# IR_remote_2_1.net
KiCad netlist of a schematic drawn in EAGLE
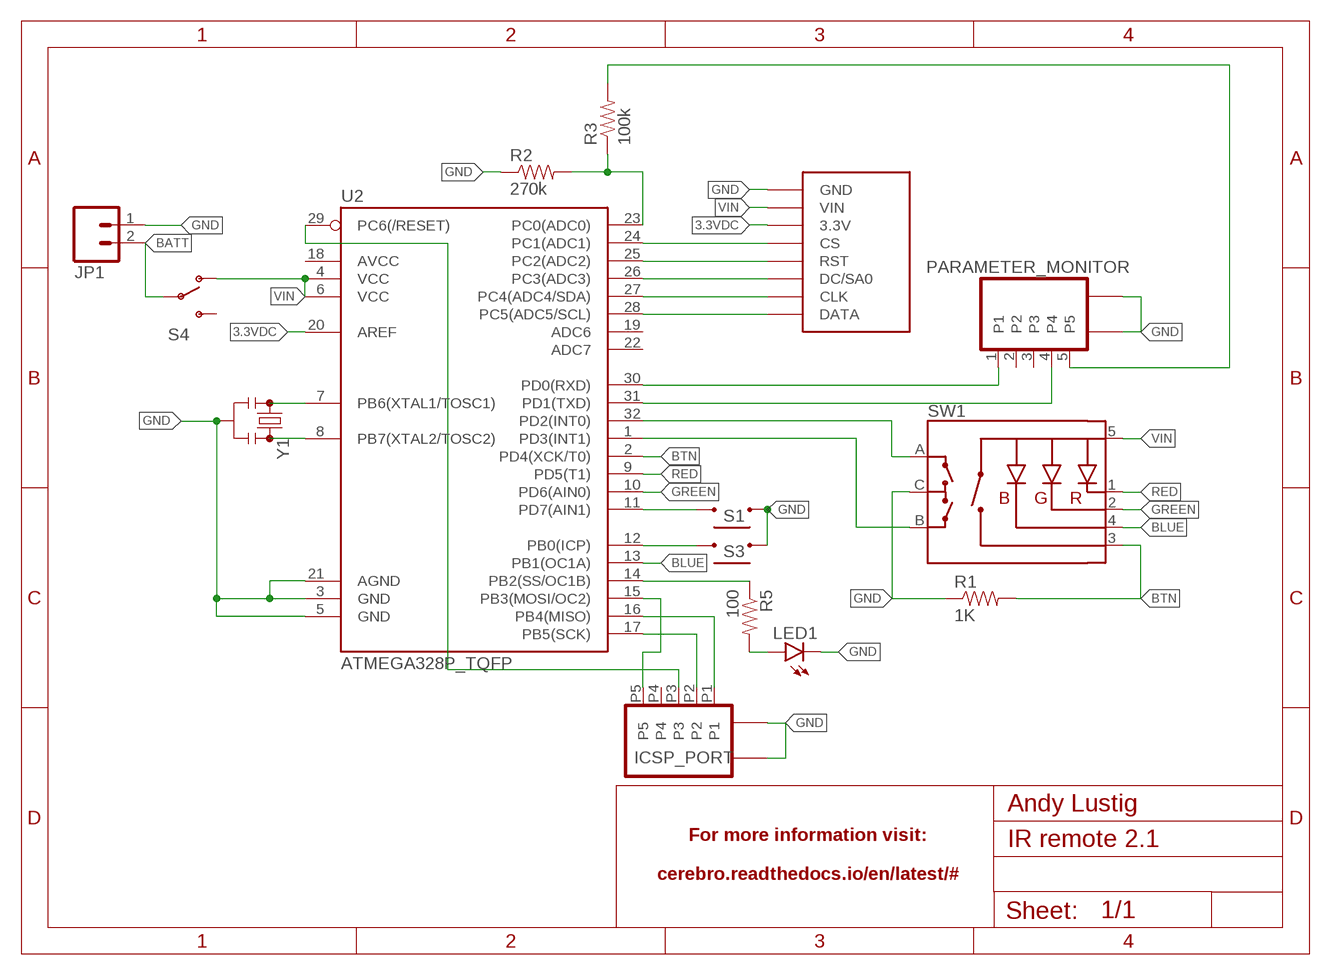
[diagram p0: schematic, sheet 1]

(export (version "E")
  (design (tool "Eeschema 10.0.6"))
  (components
    (comp (ref "ICSP_PORT")
      (value "USB_SOCKET_MICRO_VERTREINFORCED")
      (footprint "eagle-import:USB_HORZ_REINFORCED_MICRO")
      (libsource (lib "eagle-import") (part "USB_SOCKET_MICRO_VERTREINFORCED"))
    )
    (comp (ref "JP1")
      (value "M02JST-PTH-2")
      (footprint "eagle-import:JST-2-PTH")
      (libsource (lib "eagle-import") (part "M02JST-PTH-2"))
    )
    (comp (ref "LED1")
      (value "LED5MM-KIT")
      (footprint "eagle-import:LED5MM-KIT")
      (libsource (lib "eagle-import") (part "LED5MM-KIT"))
    )
    (comp (ref "PARAMETER_MONITOR")
      (value "USB_MICROB_PLUG-PTH2")
      (footprint "eagle-import:MICRO-B-TH")
      (libsource (lib "eagle-import") (part "USB_MICROB_PLUG-PTH2"))
    )
    (comp (ref "R1")
      (value "1K")
      (footprint "eagle-import:AXIAL-0.1")
      (libsource (lib "eagle-import") (part "RESISTORPTH-1/4W-VERT"))
    )
    (comp (ref "R2")
      (value "270k")
      (footprint "eagle-import:AXIAL-0.1")
      (libsource (lib "eagle-import") (part "RESISTORPTH-1/4W-VERT"))
    )
    (comp (ref "R3")
      (value "100k")
      (footprint "eagle-import:AXIAL-0.1")
      (libsource (lib "eagle-import") (part "RESISTORPTH-1/4W-VERT"))
    )
    (comp (ref "R5")
      (value "100")
      (footprint "eagle-import:AXIAL-0.1")
      (libsource (lib "eagle-import") (part "RESISTORPTH-1/4W-VERT"))
    )
    (comp (ref "S1")
      (value "SWITCH-MOMENTARY-2-CLOSED")
      (footprint "eagle-import:TACTILE-PTH-12MM")
      (libsource (lib "eagle-import") (part "SWITCH-MOMENTARY-2-CLOSED"))
    )
    (comp (ref "S3")
      (value "SWITCH-MOMENTARY-2-CLOSED")
      (footprint "eagle-import:TACTILE-PTH-12MM")
      (libsource (lib "eagle-import") (part "SWITCH-MOMENTARY-2-CLOSED"))
    )
    (comp (ref "S4")
      (value "SWITCH-SPDT")
      (footprint "eagle-import:TOGGLE")
      (libsource (lib "eagle-import") (part "SWITCH-SPDT"))
    )
    (comp (ref "SW1")
      (value "ENCODER_RGB_CAKIT")
      (footprint "eagle-import:ENCODER_LED_3_KIT")
      (libsource (lib "eagle-import") (part "ENCODER_RGB_CAKIT"))
    )
    (comp (ref "U$1")
      (value "OLED_DISPLAY")
      (footprint "eagle-import:OLED_DISPLAY")
      (libsource (lib "eagle-import") (part "OLED_DISPLAY"))
    )
    (comp (ref "U2")
      (value "ATMEGA328P_TQFP")
      (footprint "eagle-import:TQFP32-08")
      (libsource (lib "eagle-import") (part "ATMEGA328P_TQFP"))
    )
    (comp (ref "Y1")
      (value "RESONATORPTH")
      (footprint "eagle-import:RESONATOR-PTH")
      (libsource (lib "eagle-import") (part "RESONATORPTH"))
    )
  )
  (nets
    (net (code "1") (name "3.3VDC") (class "Default")
      (node (ref "U$1") (pin "3V3") (pinfunction "3.3V_3V3") (pintype "power_in"))
      (node (ref "U2") (pin "20") (pinfunction "AREF_20") (pintype "bidirectional"))
    )
    (net (code "2") (name "BATT") (class "Default")
      (node (ref "JP1") (pin "2") (pinfunction "2_2") (pintype "passive"))
      (node (ref "S4") (pin "P$2") (pinfunction "P_P$2") (pintype "passive"))
    )
    (net (code "3") (name "BLUE") (class "Default")
      (node (ref "SW1") (pin "4") (pinfunction "-B_4") (pintype "passive"))
      (node (ref "U2") (pin "13") (pinfunction "PB1(OC1A)_13") (pintype "bidirectional"))
    )
    (net (code "4") (name "BTN") (class "Default")
      (node (ref "R1") (pin "P$2") (pinfunction "2_P$2") (pintype "passive"))
      (node (ref "SW1") (pin "3") (pinfunction "SW_3") (pintype "passive"))
      (node (ref "U2") (pin "2") (pinfunction "PD4(XCK/T0)_2") (pintype "bidirectional"))
    )
    (net (code "5") (name "GND") (class "Default")
      (node (ref "ICSP_PORT") (pin "G1") (pinfunction "P$1_G1") (pintype "bidirectional"))
      (node (ref "ICSP_PORT") (pin "G2") (pinfunction "P$1_G2") (pintype "bidirectional"))
      (node (ref "ICSP_PORT") (pin "P$1") (pinfunction "P$2_P$1") (pintype "bidirectional"))
      (node (ref "ICSP_PORT") (pin "P$2") (pinfunction "P$2_P$2") (pintype "bidirectional"))
      (node (ref "JP1") (pin "1") (pinfunction "1_1") (pintype "passive"))
      (node (ref "LED1") (pin "K") (pinfunction "C_K") (pintype "passive"))
      (node (ref "PARAMETER_MONITOR") (pin "P$1") (pinfunction "P$1_P$1") (pintype "bidirectional"))
      (node (ref "PARAMETER_MONITOR") (pin "P$2") (pinfunction "P$2_P$2") (pintype "bidirectional"))
      (node (ref "R1") (pin "P$1") (pinfunction "1_P$1") (pintype "passive"))
      (node (ref "R2") (pin "P$1") (pinfunction "1_P$1") (pintype "passive"))
      (node (ref "S1") (pin "3") (pinfunction "2_3") (pintype "passive"))
      (node (ref "S3") (pin "3") (pinfunction "2_3") (pintype "passive"))
      (node (ref "SW1") (pin "C") (pinfunction "C_C") (pintype "bidirectional"))
      (node (ref "U$1") (pin "GND") (pinfunction "GND_GND") (pintype "bidirectional"))
      (node (ref "U2") (pin "21") (pinfunction "AGND_21") (pintype "bidirectional"))
      (node (ref "U2") (pin "3") (pinfunction "GND_3") (pintype "bidirectional"))
      (node (ref "U2") (pin "5") (pinfunction "GND_5") (pintype "bidirectional"))
      (node (ref "Y1") (pin "2") (pinfunction "2_2") (pintype "passive"))
    )
    (net (code "6") (name "GREEN") (class "Default")
      (node (ref "SW1") (pin "2") (pinfunction "-G_2") (pintype "passive"))
      (node (ref "U2") (pin "10") (pinfunction "PD6(AIN0)_10") (pintype "bidirectional"))
    )
    (net (code "7") (name "Net-(PARAMETER_MONITOR-P1)") (class "Default")
      (node (ref "PARAMETER_MONITOR") (pin "1") (pinfunction "P1_1") (pintype "bidirectional"))
      (node (ref "U2") (pin "30") (pinfunction "PD0(RXD)_30") (pintype "bidirectional"))
    )
    (net (code "8") (name "Net-(PARAMETER_MONITOR-P4)") (class "Default")
      (node (ref "PARAMETER_MONITOR") (pin "4") (pinfunction "P4_4") (pintype "bidirectional"))
      (node (ref "U2") (pin "31") (pinfunction "PD1(TXD)_31") (pintype "bidirectional"))
    )
    (net (code "9") (name "Net-(PARAMETER_MONITOR-P5)") (class "Default")
      (node (ref "PARAMETER_MONITOR") (pin "5") (pinfunction "P5_5") (pintype "bidirectional"))
      (node (ref "R3") (pin "P$2") (pinfunction "2_P$2") (pintype "passive"))
    )
    (net (code "10") (name "Net-(R2-2)") (class "Default")
      (node (ref "R2") (pin "P$2") (pinfunction "2_P$2") (pintype "passive"))
      (node (ref "R3") (pin "P$1") (pinfunction "1_P$1") (pintype "passive"))
      (node (ref "U2") (pin "23") (pinfunction "PC0(ADC0)_23") (pintype "bidirectional"))
    )
    (net (code "11") (name "Net-(R5-1)") (class "Default")
      (node (ref "R5") (pin "P$1") (pinfunction "1_P$1") (pintype "passive"))
      (node (ref "U2") (pin "14") (pinfunction "PB2(SS/OC1B)_14") (pintype "bidirectional"))
    )
    (net (code "12") (name "Net-(R5-2)") (class "Default")
      (node (ref "LED1") (pin "A") (pinfunction "A_A") (pintype "passive"))
      (node (ref "R5") (pin "P$2") (pinfunction "2_P$2") (pintype "passive"))
    )
    (net (code "13") (name "Net-(U$1-DC{slash}SA0)") (class "Default")
      (node (ref "U$1") (pin "DC") (pinfunction "DC/SA0_DC") (pintype "bidirectional"))
      (node (ref "U2") (pin "26") (pinfunction "PC3(ADC3)_26") (pintype "bidirectional"))
    )
    (net (code "14") (name "Net-(U2-PB0(ICP))") (class "Default")
      (node (ref "S3") (pin "1") (pinfunction "1_1") (pintype "passive"))
      (node (ref "U2") (pin "12") (pinfunction "PB0(ICP)_12") (pintype "bidirectional"))
    )
    (net (code "15") (name "Net-(U2-PB3(MOSI{slash}OC2))") (class "Default")
      (node (ref "ICSP_PORT") (pin "P5") (pinfunction "P5_P5") (pintype "bidirectional"))
      (node (ref "U2") (pin "15") (pinfunction "PB3(MOSI/OC2)_15") (pintype "bidirectional"))
    )
    (net (code "16") (name "Net-(U2-PB4(MISO))") (class "Default")
      (node (ref "ICSP_PORT") (pin "P1") (pinfunction "P1_P1") (pintype "bidirectional"))
      (node (ref "U2") (pin "16") (pinfunction "PB4(MISO)_16") (pintype "bidirectional"))
    )
    (net (code "17") (name "Net-(U2-PB5(SCK))") (class "Default")
      (node (ref "ICSP_PORT") (pin "P2") (pinfunction "P2_P2") (pintype "bidirectional"))
      (node (ref "U2") (pin "17") (pinfunction "PB5(SCK)_17") (pintype "bidirectional"))
    )
    (net (code "18") (name "Net-(U2-PB6(XTAL1{slash}TOSC1))") (class "Default")
      (node (ref "U2") (pin "7") (pinfunction "PB6(XTAL1/TOSC1)_7") (pintype "bidirectional"))
      (node (ref "Y1") (pin "1") (pinfunction "1_1") (pintype "passive"))
    )
    (net (code "19") (name "Net-(U2-PB7(XTAL2{slash}TOSC2))") (class "Default")
      (node (ref "U2") (pin "8") (pinfunction "PB7(XTAL2/TOSC2)_8") (pintype "bidirectional"))
      (node (ref "Y1") (pin "3") (pinfunction "3_3") (pintype "passive"))
    )
    (net (code "20") (name "Net-(U2-PC1(ADC1))") (class "Default")
      (node (ref "U$1") (pin "CS") (pinfunction "CS_CS") (pintype "bidirectional"))
      (node (ref "U2") (pin "24") (pinfunction "PC1(ADC1)_24") (pintype "bidirectional"))
    )
    (net (code "21") (name "Net-(U2-PC2(ADC2))") (class "Default")
      (node (ref "U$1") (pin "RST") (pinfunction "RST_RST") (pintype "bidirectional"))
      (node (ref "U2") (pin "25") (pinfunction "PC2(ADC2)_25") (pintype "bidirectional"))
    )
    (net (code "22") (name "Net-(U2-PC4(ADC4{slash}SDA))") (class "Default")
      (node (ref "U$1") (pin "CLK") (pinfunction "CLK_CLK") (pintype "bidirectional"))
      (node (ref "U2") (pin "27") (pinfunction "PC4(ADC4/SDA)_27") (pintype "bidirectional"))
    )
    (net (code "23") (name "Net-(U2-PC5(ADC5{slash}SCL))") (class "Default")
      (node (ref "U$1") (pin "DATA") (pinfunction "DATA_DATA") (pintype "bidirectional"))
      (node (ref "U2") (pin "28") (pinfunction "PC5(ADC5/SCL)_28") (pintype "bidirectional"))
    )
    (net (code "24") (name "Net-(U2-PC6({slash}RESET))") (class "Default")
      (node (ref "ICSP_PORT") (pin "P3") (pinfunction "P3_P3") (pintype "bidirectional"))
      (node (ref "U2") (pin "29") (pinfunction "PC6(/RESET)_29") (pintype "bidirectional"))
    )
    (net (code "25") (name "Net-(U2-PD2(INT0))") (class "Default")
      (node (ref "SW1") (pin "A") (pinfunction "A_A") (pintype "bidirectional"))
      (node (ref "U2") (pin "32") (pinfunction "PD2(INT0)_32") (pintype "bidirectional"))
    )
    (net (code "26") (name "Net-(U2-PD3(INT1))") (class "Default")
      (node (ref "SW1") (pin "B") (pinfunction "B_B") (pintype "bidirectional"))
      (node (ref "U2") (pin "1") (pinfunction "PD3(INT1)_1") (pintype "bidirectional"))
    )
    (net (code "27") (name "Net-(U2-PD7(AIN1))") (class "Default")
      (node (ref "S1") (pin "1") (pinfunction "1_1") (pintype "passive"))
      (node (ref "U2") (pin "11") (pinfunction "PD7(AIN1)_11") (pintype "bidirectional"))
    )
    (net (code "28") (name "RED") (class "Default")
      (node (ref "SW1") (pin "1") (pinfunction "-R_1") (pintype "passive"))
      (node (ref "U2") (pin "9") (pinfunction "PD5(T1)_9") (pintype "bidirectional"))
    )
    (net (code "29") (name "VIN") (class "Default")
      (node (ref "S4") (pin "P$1") (pinfunction "O_P$1") (pintype "passive"))
      (node (ref "SW1") (pin "5") (pinfunction "+_5") (pintype "passive"))
      (node (ref "U$1") (pin "VIN") (pinfunction "VIN_VIN") (pintype "power_in"))
      (node (ref "U2") (pin "4") (pinfunction "VCC_4") (pintype "bidirectional"))
      (node (ref "U2") (pin "6") (pinfunction "VCC_6") (pintype "bidirectional"))
    )
    (net (code "30") (name "unconnected-(ICSP_PORT-PadP4)") (class "Default")
      (node (ref "ICSP_PORT") (pin "P4") (pinfunction "P4_P4") (pintype "bidirectional"))
    )
    (net (code "31") (name "unconnected-(PARAMETER_MONITOR-P2-Pad2)") (class "Default")
      (node (ref "PARAMETER_MONITOR") (pin "2") (pinfunction "P2_2") (pintype "bidirectional"))
    )
    (net (code "32") (name "unconnected-(PARAMETER_MONITOR-P3-Pad3)") (class "Default")
      (node (ref "PARAMETER_MONITOR") (pin "3") (pinfunction "P3_3") (pintype "bidirectional"))
    )
    (net (code "33") (name "unconnected-(S4-S-PadP$3)") (class "Default")
      (node (ref "S4") (pin "P$3") (pinfunction "S_P$3") (pintype "passive"))
    )
    (net (code "34") (name "unconnected-(U2-ADC6-Pad19)") (class "Default")
      (node (ref "U2") (pin "19") (pinfunction "ADC6_19") (pintype "bidirectional"))
    )
    (net (code "35") (name "unconnected-(U2-ADC7-Pad22)") (class "Default")
      (node (ref "U2") (pin "22") (pinfunction "ADC7_22") (pintype "bidirectional"))
    )
    (net (code "36") (name "unconnected-(U2-AVCC-Pad18)") (class "Default")
      (node (ref "U2") (pin "18") (pinfunction "AVCC_18") (pintype "bidirectional"))
    )
  )
)
